# VCA.net
KiCad netlist of a schematic drawn in EAGLE
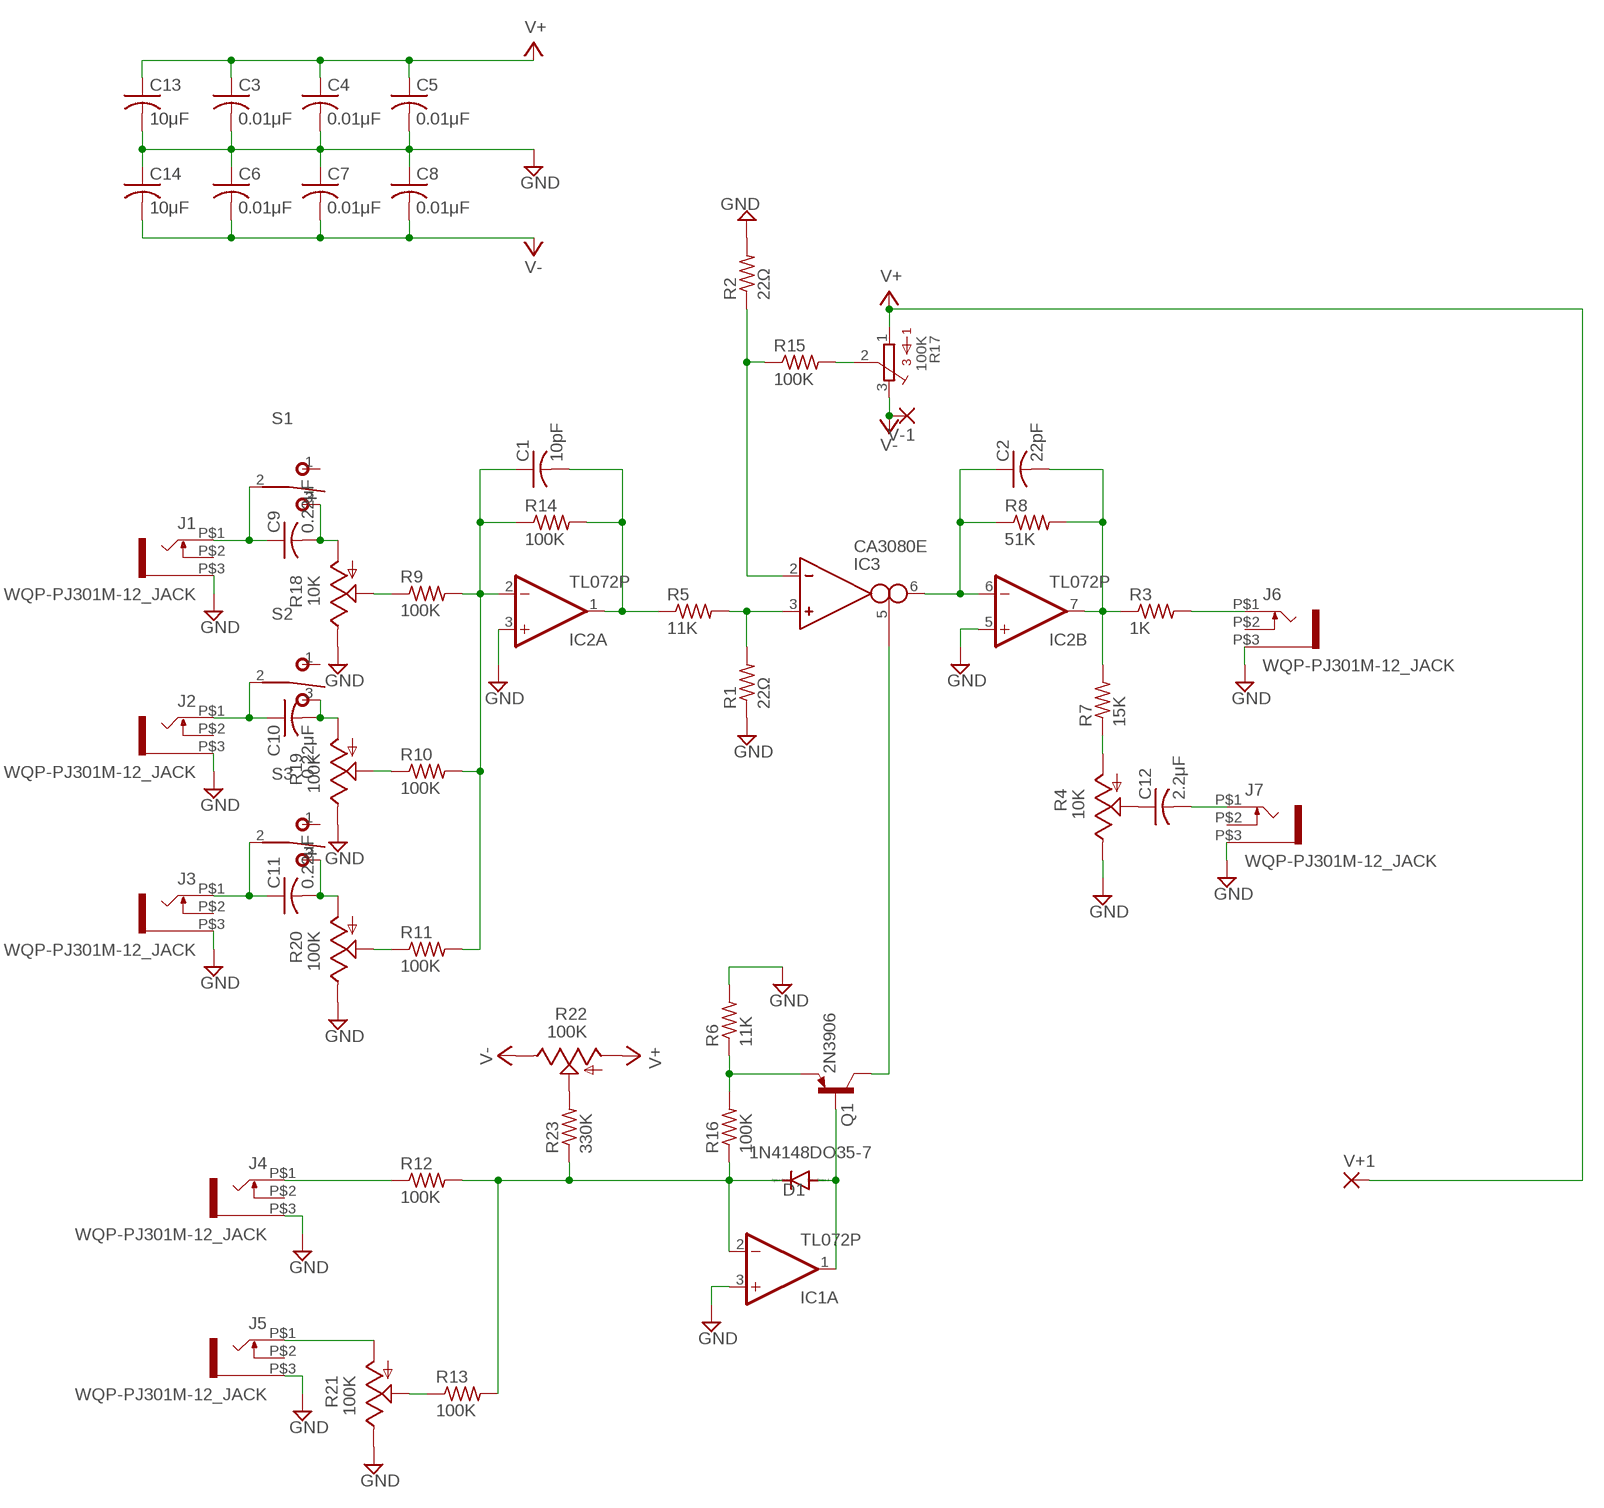
[diagram p0: schematic, sheet 1]

(export (version "E")
  (design (tool "Eeschema 10.0.6"))
  (components
    (comp (ref "C1")
      (value "10pF")
      (footprint "eagle-import:C025-024X044")
      (libsource (lib "eagle-import") (part "C-US025-024X044"))
    )
    (comp (ref "C2")
      (value "22pF")
      (footprint "eagle-import:C025-024X044")
      (libsource (lib "eagle-import") (part "C-US025-024X044"))
    )
    (comp (ref "C3")
      (value "0.01μF")
      (footprint "eagle-import:C025-024X044")
      (libsource (lib "eagle-import") (part "C-US025-024X044"))
    )
    (comp (ref "C4")
      (value "0.01μF")
      (footprint "eagle-import:C025-024X044")
      (libsource (lib "eagle-import") (part "C-US025-024X044"))
    )
    (comp (ref "C5")
      (value "0.01μF")
      (footprint "eagle-import:C025-024X044")
      (libsource (lib "eagle-import") (part "C-US025-024X044"))
    )
    (comp (ref "C6")
      (value "0.01μF")
      (footprint "eagle-import:C025-024X044")
      (libsource (lib "eagle-import") (part "C-US025-024X044"))
    )
    (comp (ref "C7")
      (value "0.01μF")
      (footprint "eagle-import:C025-024X044")
      (libsource (lib "eagle-import") (part "C-US025-024X044"))
    )
    (comp (ref "C8")
      (value "0.01μF")
      (footprint "eagle-import:C025-024X044")
      (libsource (lib "eagle-import") (part "C-US025-024X044"))
    )
    (comp (ref "C9")
      (value "0.22μF")
      (footprint "eagle-import:C025-024X044")
      (libsource (lib "eagle-import") (part "C-US025-024X044"))
    )
    (comp (ref "C10")
      (value "0.22μF")
      (footprint "eagle-import:C025-024X044")
      (libsource (lib "eagle-import") (part "C-US025-024X044"))
    )
    (comp (ref "C11")
      (value "0.22μF")
      (footprint "eagle-import:C025-024X044")
      (libsource (lib "eagle-import") (part "C-US025-024X044"))
    )
    (comp (ref "C12")
      (value "2.2μF")
      (footprint "eagle-import:C025-024X044")
      (libsource (lib "eagle-import") (part "C-US025-024X044"))
    )
    (comp (ref "C13")
      (value "10μF")
      (footprint "eagle-import:C025-024X044")
      (libsource (lib "eagle-import") (part "C-US025-024X044"))
    )
    (comp (ref "C14")
      (value "10μF")
      (footprint "eagle-import:C025-024X044")
      (libsource (lib "eagle-import") (part "C-US025-024X044"))
    )
    (comp (ref "D1")
      (value "1N4148DO35-7")
      (footprint "eagle-import:DO35-7")
      (libsource (lib "eagle-import") (part "1N4148DO35-7"))
    )
    (comp (ref "IC1")
      (value "TL072P")
      (footprint "eagle-import:DIL08")
      (libsource (lib "eagle-import") (part "TL072P"))
    )
    (comp (ref "IC2")
      (value "TL072P")
      (footprint "eagle-import:DIL08")
      (libsource (lib "eagle-import") (part "TL072P"))
    )
    (comp (ref "IC3")
      (value "CA3080E")
      (footprint "eagle-import:DIL08")
      (libsource (lib "eagle-import") (part "CA3080E"))
    )
    (comp (ref "J1")
      (value "WQP-PJ301M-12_JACK")
      (footprint "eagle-import:WQP-PJ301M-12_JACK")
      (libsource (lib "eagle-import") (part "WQP-PJ301M-12_JACK"))
    )
    (comp (ref "J2")
      (value "WQP-PJ301M-12_JACK")
      (footprint "eagle-import:WQP-PJ301M-12_JACK")
      (libsource (lib "eagle-import") (part "WQP-PJ301M-12_JACK"))
    )
    (comp (ref "J3")
      (value "WQP-PJ301M-12_JACK")
      (footprint "eagle-import:WQP-PJ301M-12_JACK")
      (libsource (lib "eagle-import") (part "WQP-PJ301M-12_JACK"))
    )
    (comp (ref "J4")
      (value "WQP-PJ301M-12_JACK")
      (footprint "eagle-import:WQP-PJ301M-12_JACK")
      (libsource (lib "eagle-import") (part "WQP-PJ301M-12_JACK"))
    )
    (comp (ref "J5")
      (value "WQP-PJ301M-12_JACK")
      (footprint "eagle-import:WQP-PJ301M-12_JACK")
      (libsource (lib "eagle-import") (part "WQP-PJ301M-12_JACK"))
    )
    (comp (ref "J6")
      (value "WQP-PJ301M-12_JACK")
      (footprint "eagle-import:WQP-PJ301M-12_JACK")
      (libsource (lib "eagle-import") (part "WQP-PJ301M-12_JACK"))
    )
    (comp (ref "J7")
      (value "WQP-PJ301M-12_JACK")
      (footprint "eagle-import:WQP-PJ301M-12_JACK")
      (libsource (lib "eagle-import") (part "WQP-PJ301M-12_JACK"))
    )
    (comp (ref "Q1")
      (value "2N3906")
      (footprint "eagle-import:TO92")
      (libsource (lib "eagle-import") (part "2N3906"))
    )
    (comp (ref "R1")
      (value "22Ω")
      (footprint "eagle-import:0411_15")
      (libsource (lib "eagle-import") (part "R-US_0411/15"))
    )
    (comp (ref "R2")
      (value "22Ω")
      (footprint "eagle-import:0411_15")
      (libsource (lib "eagle-import") (part "R-US_0411/15"))
    )
    (comp (ref "R3")
      (value "1K")
      (footprint "eagle-import:0411_15")
      (libsource (lib "eagle-import") (part "R-US_0411/15"))
    )
    (comp (ref "R4")
      (value "10K")
      (footprint "eagle-import:9MM_SNAP-IN_POT")
      (libsource (lib "eagle-import") (part "9MM_SNAP-IN_POT_"))
    )
    (comp (ref "R5")
      (value "11K")
      (footprint "eagle-import:0411_15")
      (libsource (lib "eagle-import") (part "R-US_0411/15"))
    )
    (comp (ref "R6")
      (value "11K")
      (footprint "eagle-import:0411_15")
      (libsource (lib "eagle-import") (part "R-US_0411/15"))
    )
    (comp (ref "R7")
      (value "15K")
      (footprint "eagle-import:0411_15")
      (libsource (lib "eagle-import") (part "R-US_0411/15"))
    )
    (comp (ref "R8")
      (value "51K")
      (footprint "eagle-import:0411_15")
      (libsource (lib "eagle-import") (part "R-US_0411/15"))
    )
    (comp (ref "R9")
      (value "100K")
      (footprint "eagle-import:0411_15")
      (libsource (lib "eagle-import") (part "R-US_0411/15"))
    )
    (comp (ref "R10")
      (value "100K")
      (footprint "eagle-import:0411_15")
      (libsource (lib "eagle-import") (part "R-US_0411/15"))
    )
    (comp (ref "R11")
      (value "100K")
      (footprint "eagle-import:0411_15")
      (libsource (lib "eagle-import") (part "R-US_0411/15"))
    )
    (comp (ref "R12")
      (value "100K")
      (footprint "eagle-import:0411_15")
      (libsource (lib "eagle-import") (part "R-US_0411/15"))
    )
    (comp (ref "R13")
      (value "100K")
      (footprint "eagle-import:0411_15")
      (libsource (lib "eagle-import") (part "R-US_0411/15"))
    )
    (comp (ref "R14")
      (value "100K")
      (footprint "eagle-import:0411_15")
      (libsource (lib "eagle-import") (part "R-US_0411/15"))
    )
    (comp (ref "R15")
      (value "100K")
      (footprint "eagle-import:0411_15")
      (libsource (lib "eagle-import") (part "R-US_0411/15"))
    )
    (comp (ref "R16")
      (value "100K")
      (footprint "eagle-import:0411_15")
      (libsource (lib "eagle-import") (part "R-US_0411/15"))
    )
    (comp (ref "R17")
      (value "100K")
      (footprint "eagle-import:3386C")
      (libsource (lib "eagle-import") (part "3386-C"))
    )
    (comp (ref "R18")
      (value "10K")
      (footprint "eagle-import:9MM_SNAP-IN_POT")
      (libsource (lib "eagle-import") (part "9MM_SNAP-IN_POT_"))
    )
    (comp (ref "R19")
      (value "100K")
      (footprint "eagle-import:9MM_SNAP-IN_POT")
      (libsource (lib "eagle-import") (part "9MM_SNAP-IN_POT_"))
    )
    (comp (ref "R20")
      (value "100K")
      (footprint "eagle-import:9MM_SNAP-IN_POT")
      (libsource (lib "eagle-import") (part "9MM_SNAP-IN_POT_"))
    )
    (comp (ref "R21")
      (value "100K")
      (footprint "eagle-import:9MM_SNAP-IN_POT")
      (libsource (lib "eagle-import") (part "9MM_SNAP-IN_POT_"))
    )
    (comp (ref "R22")
      (value "100K")
      (footprint "eagle-import:9MM_SNAP-IN_POT")
      (libsource (lib "eagle-import") (part "9MM_SNAP-IN_POT_"))
    )
    (comp (ref "R23")
      (value "330K")
      (footprint "eagle-import:0411_15")
      (libsource (lib "eagle-import") (part "R-US_0411/15"))
    )
    (comp (ref "S1")
      (value "T-80-T-SPDT-ON-OFF-ON")
      (footprint "eagle-import:M9040P")
      (libsource (lib "eagle-import") (part "T-80-T-SPDT-ON-OFF-ON"))
    )
    (comp (ref "S2")
      (value "T-80-T-SPDT-ON-OFF-ON")
      (footprint "eagle-import:M9040P")
      (libsource (lib "eagle-import") (part "T-80-T-SPDT-ON-OFF-ON"))
    )
    (comp (ref "S3")
      (value "T-80-T-SPDT-ON-OFF-ON")
      (footprint "eagle-import:M9040P")
      (libsource (lib "eagle-import") (part "T-80-T-SPDT-ON-OFF-ON"))
    )
    (comp (ref "V+1")
      (value "1,6/0,8")
      (footprint "eagle-import:1,6_0,8")
      (libsource (lib "eagle-import") (part "1,6/0,8"))
    )
    (comp (ref "V-1")
      (value "1,6/0,8")
      (footprint "eagle-import:1,6_0,8")
      (libsource (lib "eagle-import") (part "1,6/0,8"))
    )
  )
  (nets
    (net (code "1") (name "GND") (class "Default")
      (node (ref "C13") (pin "2") (pinfunction "2_2") (pintype "passive"))
      (node (ref "C14") (pin "1") (pinfunction "1_1") (pintype "passive"))
      (node (ref "C3") (pin "2") (pinfunction "2_2") (pintype "passive"))
      (node (ref "C4") (pin "2") (pinfunction "2_2") (pintype "passive"))
      (node (ref "C5") (pin "2") (pinfunction "2_2") (pintype "passive"))
      (node (ref "C6") (pin "1") (pinfunction "1_1") (pintype "passive"))
      (node (ref "C7") (pin "1") (pinfunction "1_1") (pintype "passive"))
      (node (ref "C8") (pin "1") (pinfunction "1_1") (pintype "passive"))
      (node (ref "IC1") (pin "3") (pinfunction "+IN_3") (pintype "input"))
      (node (ref "IC2") (pin "3") (pinfunction "+IN_3") (pintype "input"))
      (node (ref "IC2") (pin "5") (pinfunction "+IN_5") (pintype "input"))
      (node (ref "J1") (pin "P$3") (pinfunction "1_P$3") (pintype "passive"))
      (node (ref "J2") (pin "P$3") (pinfunction "1_P$3") (pintype "passive"))
      (node (ref "J3") (pin "P$3") (pinfunction "1_P$3") (pintype "passive"))
      (node (ref "J4") (pin "P$3") (pinfunction "1_P$3") (pintype "passive"))
      (node (ref "J5") (pin "P$3") (pinfunction "1_P$3") (pintype "passive"))
      (node (ref "J6") (pin "P$3") (pinfunction "1_P$3") (pintype "passive"))
      (node (ref "J7") (pin "P$3") (pinfunction "1_P$3") (pintype "passive"))
      (node (ref "R1") (pin "1") (pinfunction "1_1") (pintype "passive"))
      (node (ref "R18") (pin "3") (pinfunction "E_3") (pintype "passive"))
      (node (ref "R19") (pin "3") (pinfunction "E_3") (pintype "passive"))
      (node (ref "R2") (pin "2") (pinfunction "2_2") (pintype "passive"))
      (node (ref "R20") (pin "3") (pinfunction "E_3") (pintype "passive"))
      (node (ref "R21") (pin "3") (pinfunction "E_3") (pintype "passive"))
      (node (ref "R4") (pin "3") (pinfunction "E_3") (pintype "passive"))
      (node (ref "R6") (pin "2") (pinfunction "2_2") (pintype "passive"))
    )
    (net (code "2") (name "Net-(IC1A--IN)") (class "Default")
      (node (ref "D1") (pin "C") (pinfunction "C_C") (pintype "passive"))
      (node (ref "IC1") (pin "2") (pinfunction "-IN_2") (pintype "input"))
      (node (ref "R12") (pin "2") (pinfunction "2_2") (pintype "passive"))
      (node (ref "R13") (pin "2") (pinfunction "2_2") (pintype "passive"))
      (node (ref "R16") (pin "1") (pinfunction "1_1") (pintype "passive"))
      (node (ref "R23") (pin "1") (pinfunction "1_1") (pintype "passive"))
    )
    (net (code "3") (name "Net-(IC1A-OUT)") (class "Default")
      (node (ref "D1") (pin "A") (pinfunction "A_A") (pintype "passive"))
      (node (ref "IC1") (pin "1") (pinfunction "OUT_1") (pintype "output"))
      (node (ref "Q1") (pin "2") (pinfunction "B_2") (pintype "passive"))
    )
    (net (code "4") (name "Net-(IC2A--IN)") (class "Default")
      (node (ref "C1") (pin "1") (pinfunction "1_1") (pintype "passive"))
      (node (ref "IC2") (pin "2") (pinfunction "-IN_2") (pintype "input"))
      (node (ref "R10") (pin "2") (pinfunction "2_2") (pintype "passive"))
      (node (ref "R11") (pin "2") (pinfunction "2_2") (pintype "passive"))
      (node (ref "R14") (pin "1") (pinfunction "1_1") (pintype "passive"))
      (node (ref "R9") (pin "2") (pinfunction "2_2") (pintype "passive"))
    )
    (net (code "5") (name "Net-(IC2A-OUT)") (class "Default")
      (node (ref "C1") (pin "2") (pinfunction "2_2") (pintype "passive"))
      (node (ref "IC2") (pin "1") (pinfunction "OUT_1") (pintype "output"))
      (node (ref "R14") (pin "2") (pinfunction "2_2") (pintype "passive"))
      (node (ref "R5") (pin "1") (pinfunction "1_1") (pintype "passive"))
    )
    (net (code "6") (name "Net-(IC2B--IN)") (class "Default")
      (node (ref "C2") (pin "1") (pinfunction "1_1") (pintype "passive"))
      (node (ref "IC2") (pin "6") (pinfunction "-IN_6") (pintype "input"))
      (node (ref "IC3") (pin "6") (pinfunction "OUT_6") (pintype "output"))
      (node (ref "R8") (pin "1") (pinfunction "1_1") (pintype "passive"))
    )
    (net (code "7") (name "Net-(IC2B-OUT)") (class "Default")
      (node (ref "C2") (pin "2") (pinfunction "2_2") (pintype "passive"))
      (node (ref "IC2") (pin "7") (pinfunction "OUT_7") (pintype "output"))
      (node (ref "R3") (pin "1") (pinfunction "1_1") (pintype "passive"))
      (node (ref "R7") (pin "2") (pinfunction "2_2") (pintype "passive"))
      (node (ref "R8") (pin "2") (pinfunction "2_2") (pintype "passive"))
    )
    (net (code "8") (name "Net-(IC3A-IN_N)") (class "Default")
      (node (ref "IC3") (pin "2") (pinfunction "IN_N_2") (pintype "input"))
      (node (ref "R15") (pin "1") (pinfunction "1_1") (pintype "passive"))
      (node (ref "R2") (pin "1") (pinfunction "1_1") (pintype "passive"))
    )
    (net (code "9") (name "Net-(IC3A-IN_P)") (class "Default")
      (node (ref "IC3") (pin "3") (pinfunction "IN_P_3") (pintype "input"))
      (node (ref "R1") (pin "2") (pinfunction "2_2") (pintype "passive"))
      (node (ref "R5") (pin "2") (pinfunction "2_2") (pintype "passive"))
    )
    (net (code "10") (name "Net-(IC3A-I_BIAS)") (class "Default")
      (node (ref "IC3") (pin "5") (pinfunction "I_BIAS_5") (pintype "input"))
      (node (ref "Q1") (pin "1") (pinfunction "C_1") (pintype "passive"))
    )
    (net (code "11") (name "Net-(J1-2)") (class "Default")
      (node (ref "C9") (pin "1") (pinfunction "1_1") (pintype "passive"))
      (node (ref "J1") (pin "P$1") (pinfunction "2_P$1") (pintype "passive"))
      (node (ref "S1") (pin "2") (pinfunction "P_2") (pintype "passive"))
    )
    (net (code "12") (name "Net-(J2-2)") (class "Default")
      (node (ref "C10") (pin "1") (pinfunction "1_1") (pintype "passive"))
      (node (ref "J2") (pin "P$1") (pinfunction "2_P$1") (pintype "passive"))
      (node (ref "S2") (pin "2") (pinfunction "P_2") (pintype "passive"))
    )
    (net (code "13") (name "Net-(J3-2)") (class "Default")
      (node (ref "C11") (pin "1") (pinfunction "1_1") (pintype "passive"))
      (node (ref "J3") (pin "P$1") (pinfunction "2_P$1") (pintype "passive"))
      (node (ref "S3") (pin "2") (pinfunction "P_2") (pintype "passive"))
    )
    (net (code "14") (name "Net-(J4-2)") (class "Default")
      (node (ref "J4") (pin "P$1") (pinfunction "2_P$1") (pintype "passive"))
      (node (ref "R12") (pin "1") (pinfunction "1_1") (pintype "passive"))
    )
    (net (code "15") (name "Net-(J5-2)") (class "Default")
      (node (ref "J5") (pin "P$1") (pinfunction "2_P$1") (pintype "passive"))
      (node (ref "R21") (pin "1") (pinfunction "A_1") (pintype "passive"))
    )
    (net (code "16") (name "Net-(J6-2)") (class "Default")
      (node (ref "J6") (pin "P$1") (pinfunction "2_P$1") (pintype "passive"))
      (node (ref "R3") (pin "2") (pinfunction "2_2") (pintype "passive"))
    )
    (net (code "17") (name "Net-(J7-2)") (class "Default")
      (node (ref "C12") (pin "2") (pinfunction "2_2") (pintype "passive"))
      (node (ref "J7") (pin "P$1") (pinfunction "2_P$1") (pintype "passive"))
    )
    (net (code "18") (name "Net-(Q1-E)") (class "Default")
      (node (ref "Q1") (pin "3") (pinfunction "E_3") (pintype "passive"))
      (node (ref "R16") (pin "2") (pinfunction "2_2") (pintype "passive"))
      (node (ref "R6") (pin "1") (pinfunction "1_1") (pintype "passive"))
    )
    (net (code "19") (name "Net-(R4-A)") (class "Default")
      (node (ref "R4") (pin "1") (pinfunction "A_1") (pintype "passive"))
      (node (ref "R7") (pin "1") (pinfunction "1_1") (pintype "passive"))
    )
    (net (code "20") (name "Net-(R4-S)") (class "Default")
      (node (ref "C12") (pin "1") (pinfunction "1_1") (pintype "passive"))
      (node (ref "R4") (pin "2") (pinfunction "S_2") (pintype "passive"))
    )
    (net (code "21") (name "Net-(R15-Pad2)") (class "Default")
      (node (ref "R15") (pin "2") (pinfunction "2_2") (pintype "passive"))
      (node (ref "R17") (pin "2") (pinfunction "2_2") (pintype "passive"))
    )
    (net (code "22") (name "Net-(R18-A)") (class "Default")
      (node (ref "C9") (pin "2") (pinfunction "2_2") (pintype "passive"))
      (node (ref "R18") (pin "1") (pinfunction "A_1") (pintype "passive"))
      (node (ref "S1") (pin "3") (pinfunction "S_3") (pintype "passive"))
    )
    (net (code "23") (name "Net-(R18-S)") (class "Default")
      (node (ref "R18") (pin "2") (pinfunction "S_2") (pintype "passive"))
      (node (ref "R9") (pin "1") (pinfunction "1_1") (pintype "passive"))
    )
    (net (code "24") (name "Net-(R19-A)") (class "Default")
      (node (ref "C10") (pin "2") (pinfunction "2_2") (pintype "passive"))
      (node (ref "R19") (pin "1") (pinfunction "A_1") (pintype "passive"))
      (node (ref "S2") (pin "3") (pinfunction "S_3") (pintype "passive"))
    )
    (net (code "25") (name "Net-(R19-S)") (class "Default")
      (node (ref "R10") (pin "1") (pinfunction "1_1") (pintype "passive"))
      (node (ref "R19") (pin "2") (pinfunction "S_2") (pintype "passive"))
    )
    (net (code "26") (name "Net-(R20-A)") (class "Default")
      (node (ref "C11") (pin "2") (pinfunction "2_2") (pintype "passive"))
      (node (ref "R20") (pin "1") (pinfunction "A_1") (pintype "passive"))
      (node (ref "S3") (pin "3") (pinfunction "S_3") (pintype "passive"))
    )
    (net (code "27") (name "Net-(R20-S)") (class "Default")
      (node (ref "R11") (pin "1") (pinfunction "1_1") (pintype "passive"))
      (node (ref "R20") (pin "2") (pinfunction "S_2") (pintype "passive"))
    )
    (net (code "28") (name "Net-(R21-S)") (class "Default")
      (node (ref "R13") (pin "1") (pinfunction "1_1") (pintype "passive"))
      (node (ref "R21") (pin "2") (pinfunction "S_2") (pintype "passive"))
    )
    (net (code "29") (name "Net-(R22-S)") (class "Default")
      (node (ref "R22") (pin "2") (pinfunction "S_2") (pintype "passive"))
      (node (ref "R23") (pin "2") (pinfunction "2_2") (pintype "passive"))
    )
    (net (code "30") (name "V+") (class "Default")
      (node (ref "C13") (pin "1") (pinfunction "1_1") (pintype "passive"))
      (node (ref "C3") (pin "1") (pinfunction "1_1") (pintype "passive"))
      (node (ref "C4") (pin "1") (pinfunction "1_1") (pintype "passive"))
      (node (ref "C5") (pin "1") (pinfunction "1_1") (pintype "passive"))
      (node (ref "R17") (pin "1") (pinfunction "1_1") (pintype "passive"))
      (node (ref "R22") (pin "1") (pinfunction "A_1") (pintype "passive"))
      (node (ref "V+1") (pin "1") (pinfunction "P_1") (pintype "passive"))
    )
    (net (code "31") (name "V-") (class "Default")
      (node (ref "C14") (pin "2") (pinfunction "2_2") (pintype "passive"))
      (node (ref "C6") (pin "2") (pinfunction "2_2") (pintype "passive"))
      (node (ref "C7") (pin "2") (pinfunction "2_2") (pintype "passive"))
      (node (ref "C8") (pin "2") (pinfunction "2_2") (pintype "passive"))
      (node (ref "R17") (pin "3") (pinfunction "3_3") (pintype "passive"))
      (node (ref "R22") (pin "3") (pinfunction "E_3") (pintype "passive"))
      (node (ref "V-1") (pin "1") (pinfunction "P_1") (pintype "passive"))
    )
    (net (code "32") (name "unconnected-(J1-3-PadP$2)") (class "Default")
      (node (ref "J1") (pin "P$2") (pinfunction "3_P$2") (pintype "passive"))
    )
    (net (code "33") (name "unconnected-(J2-3-PadP$2)") (class "Default")
      (node (ref "J2") (pin "P$2") (pinfunction "3_P$2") (pintype "passive"))
    )
    (net (code "34") (name "unconnected-(J3-3-PadP$2)") (class "Default")
      (node (ref "J3") (pin "P$2") (pinfunction "3_P$2") (pintype "passive"))
    )
    (net (code "35") (name "unconnected-(J4-3-PadP$2)") (class "Default")
      (node (ref "J4") (pin "P$2") (pinfunction "3_P$2") (pintype "passive"))
    )
    (net (code "36") (name "unconnected-(J5-3-PadP$2)") (class "Default")
      (node (ref "J5") (pin "P$2") (pinfunction "3_P$2") (pintype "passive"))
    )
    (net (code "37") (name "unconnected-(J6-3-PadP$2)") (class "Default")
      (node (ref "J6") (pin "P$2") (pinfunction "3_P$2") (pintype "passive"))
    )
    (net (code "38") (name "unconnected-(J7-3-PadP$2)") (class "Default")
      (node (ref "J7") (pin "P$2") (pinfunction "3_P$2") (pintype "passive"))
    )
    (net (code "39") (name "unconnected-(S1-O-Pad1)") (class "Default")
      (node (ref "S1") (pin "1") (pinfunction "O_1") (pintype "passive"))
    )
    (net (code "40") (name "unconnected-(S2-O-Pad1)") (class "Default")
      (node (ref "S2") (pin "1") (pinfunction "O_1") (pintype "passive"))
    )
    (net (code "41") (name "unconnected-(S3-O-Pad1)") (class "Default")
      (node (ref "S3") (pin "1") (pinfunction "O_1") (pintype "passive"))
    )
  )
)
